# Clock.net
KiCad netlist of a schematic drawn in Altium Designer
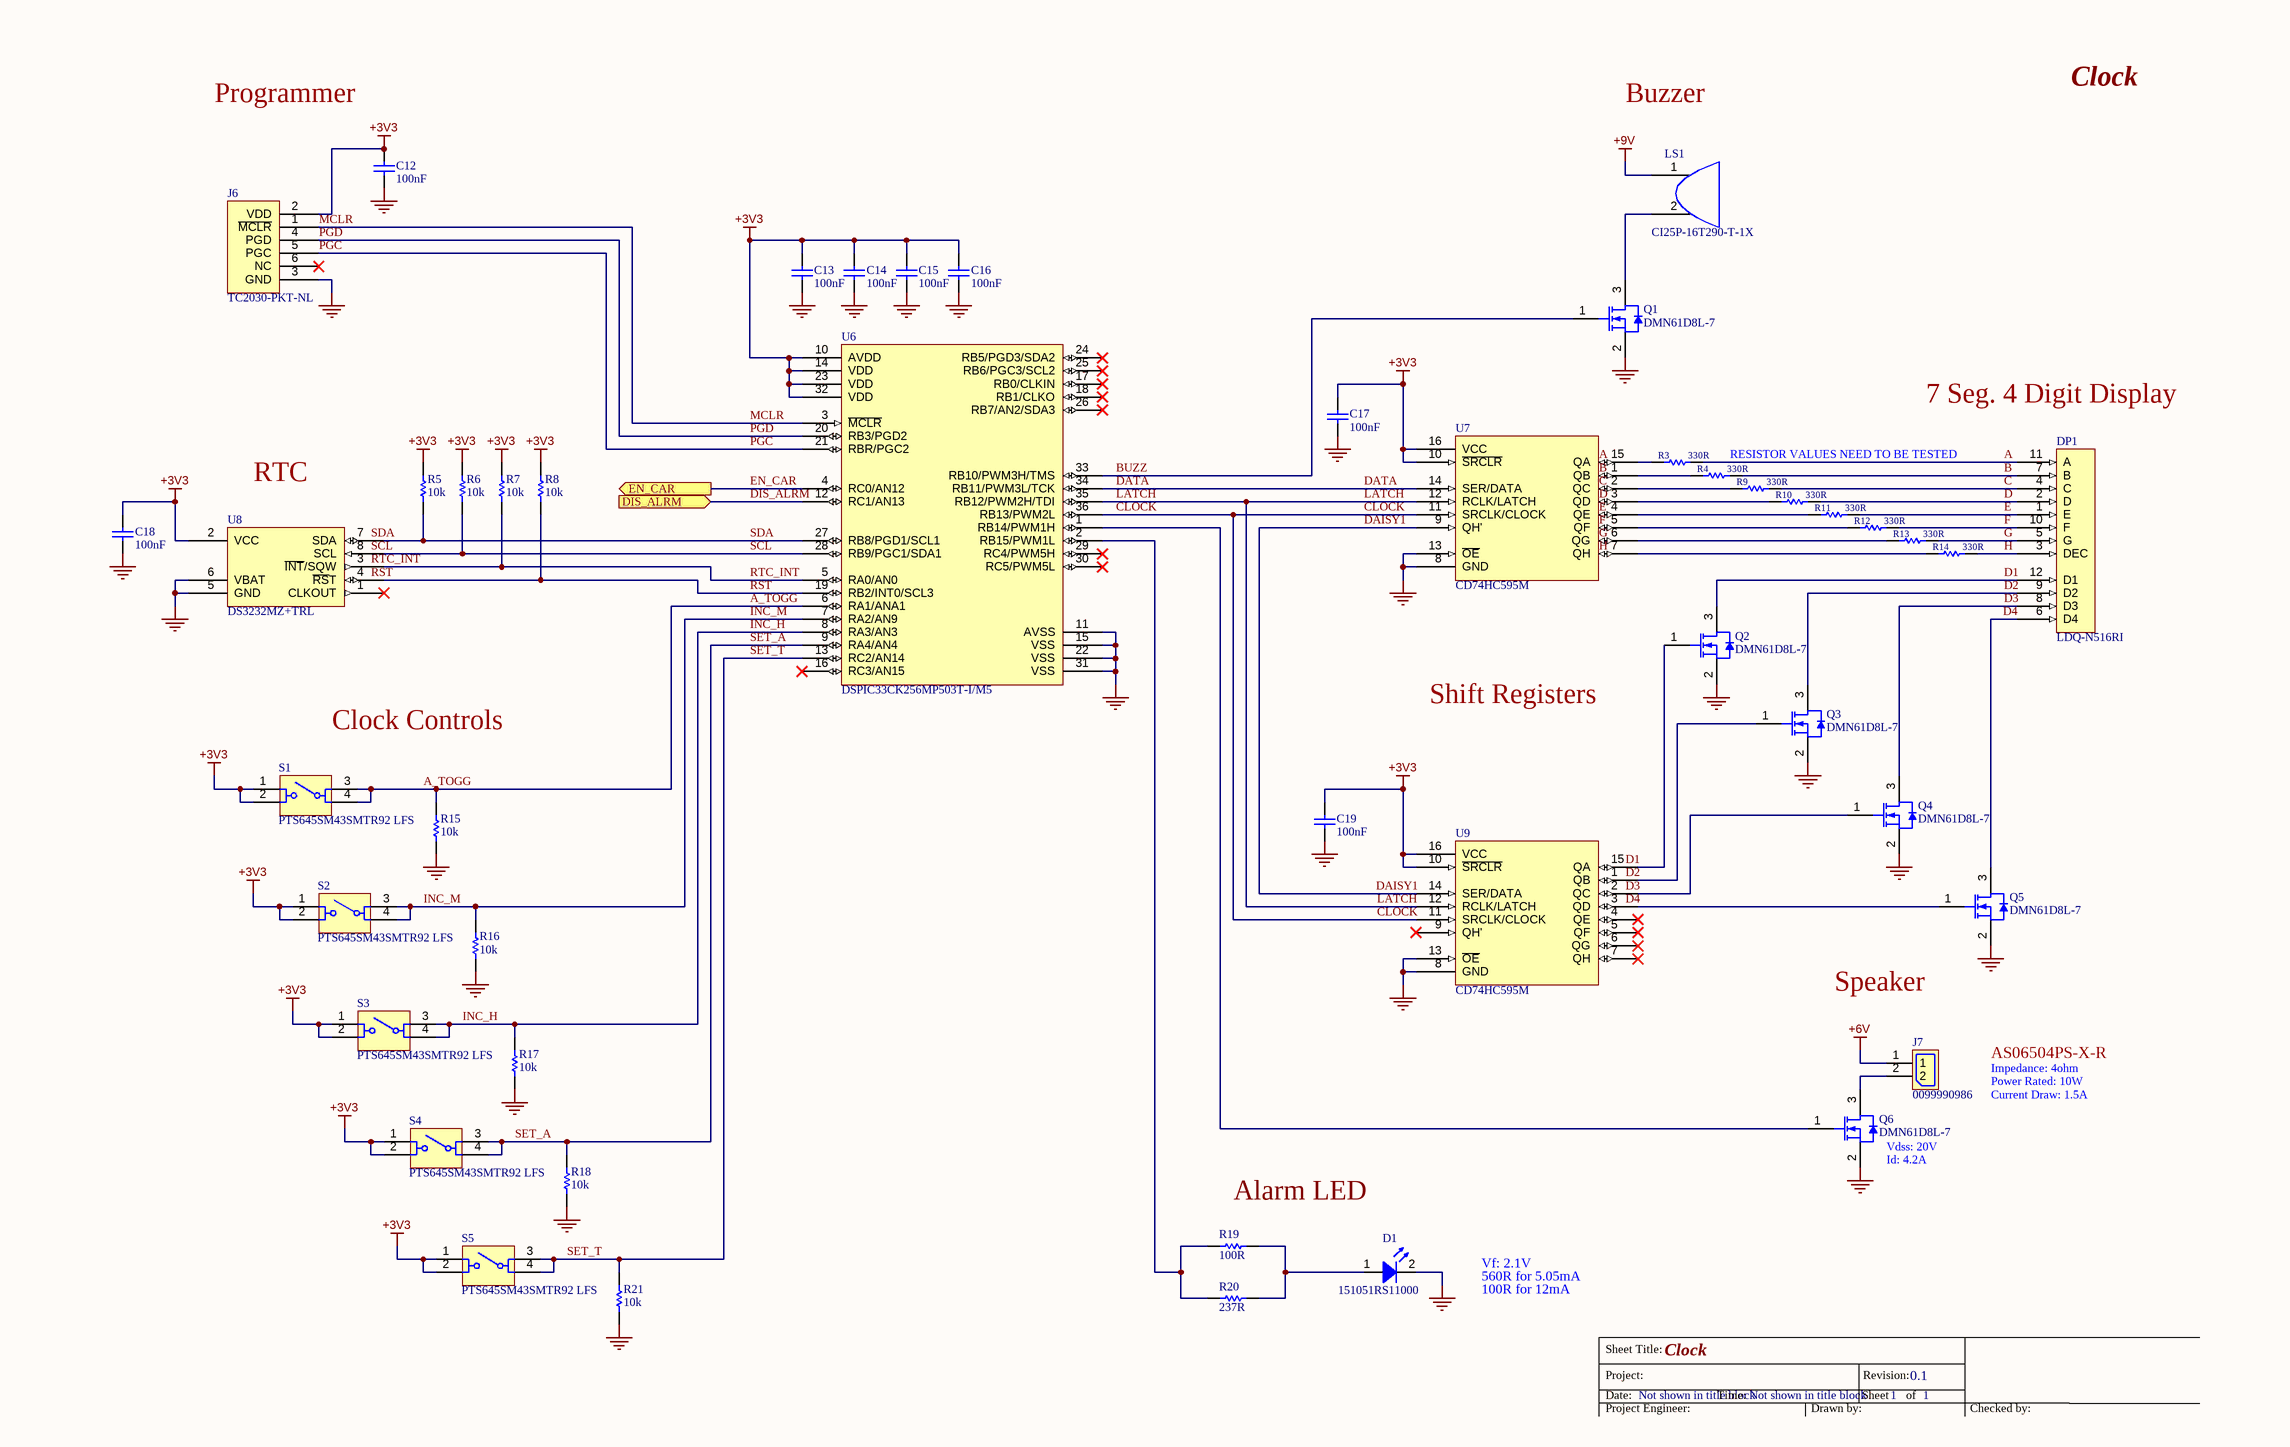
[diagram p0: Clock.SchDoc]

(export (version "E")
  (design (tool "Eeschema 10.0.6"))
  (components
    (comp (ref "C12")
      (value "100nF")
      (footprint "C0402")
      (fields (field (name "PART NUMBER") "CL05A104KA5NNNC") (field (name "MANUFACTURER") "Samsung"))
      (libsource (lib "EMRLibrary") (part "EMR_Cap"))
    )
    (comp (ref "C13")
      (value "100nF")
      (footprint "C0402")
      (fields (field (name "PART NUMBER") "CL05A104KA5NNNC") (field (name "MANUFACTURER") "Samsung"))
      (libsource (lib "EMRLibrary") (part "EMR_Cap"))
    )
    (comp (ref "C14")
      (value "100nF")
      (footprint "C0402")
      (fields (field (name "PART NUMBER") "CL05A104KA5NNNC") (field (name "MANUFACTURER") "Samsung"))
      (libsource (lib "EMRLibrary") (part "EMR_Cap"))
    )
    (comp (ref "C15")
      (value "100nF")
      (footprint "C0402")
      (fields (field (name "PART NUMBER") "CL05A104KA5NNNC") (field (name "MANUFACTURER") "Samsung"))
      (libsource (lib "EMRLibrary") (part "EMR_Cap"))
    )
    (comp (ref "C16")
      (value "100nF")
      (footprint "C0402")
      (fields (field (name "PART NUMBER") "CL05A104KA5NNNC") (field (name "MANUFACTURER") "Samsung"))
      (libsource (lib "EMRLibrary") (part "EMR_Cap"))
    )
    (comp (ref "C17")
      (value "100nF")
      (footprint "C0402")
      (fields (field (name "PART NUMBER") "CL05A104KA5NNNC") (field (name "MANUFACTURER") "Samsung"))
      (libsource (lib "EMRLibrary") (part "EMR_Cap"))
    )
    (comp (ref "C18")
      (value "100nF")
      (footprint "C0402")
      (fields (field (name "PART NUMBER") "CL05A104KA5NNNC") (field (name "MANUFACTURER") "Samsung"))
      (libsource (lib "EMRLibrary") (part "EMR_Cap"))
    )
    (comp (ref "C19")
      (value "100nF")
      (footprint "C0402")
      (fields (field (name "PART NUMBER") "CL05A104KA5NNNC") (field (name "MANUFACTURER") "Samsung"))
      (libsource (lib "EMRLibrary") (part "EMR_Cap"))
    )
    (comp (ref "D1")
      (value "151051RS11000")
      (footprint "151051RS11000")
      (fields (field (name "MANUFACTURER") "Wurth Electronics"))
      (libsource (lib "EMRLibrary") (part "EMR_LED"))
    )
    (comp (ref "DP1")
      (value "LDQ-N516RI")
      (footprint "LDQ-N516RI")
      (description "DISP 7SEG 0.56\" QUAD RED 12DIP")
      (fields (field (name "MANUFACTURER") "Lumex"))
      (libsource (lib "EMRLibrary") (part "LDQ-N516RI"))
    )
    (comp (ref "J6")
      (value "TC2030-PKT-NL")
      (footprint "TC2030-PKT-NL")
      (description "Pogo pin cable for PicKit 3")
      (libsource (lib "EMRLibrary") (part "TC2030-PKT-NL"))
    )
    (comp (ref "J7")
      (value "0099990986")
      (footprint "0099990986")
      (fields (field (name "MANUFACTURER") "Molex") (field (name "MANUFACTURER PART NUMBER") "99-99-0986"))
      (libsource (lib "EMRLibrary") (part "0099990986"))
    )
    (comp (ref "LS1")
      (value "CI25P-16T290-T-1X")
      (footprint "CI25P-16T290-T-1X")
      (description "Buzzer Piezo 12V 25.4MM Th")
      (fields (field (name "MANUFACTURER") "Challenge Electronics"))
      (libsource (lib "EMRLibrary") (part "CI25P-16T290-T-1X"))
    )
    (comp (ref "Q1")
      (value "DMN61D8L-7")
      (footprint "SOT90P240X102-3N")
      (description "MOSFET N-CH 60V 470MA SOT23")
      (fields (field (name "MANUFACTURER") "Diodes"))
      (libsource (lib "EMRLibrary") (part "BSS138L"))
    )
    (comp (ref "Q2")
      (value "DMN61D8L-7")
      (footprint "SOT90P240X102-3N")
      (description "MOSFET N-CH 60V 470MA SOT23")
      (fields (field (name "MANUFACTURER") "Diodes"))
      (libsource (lib "EMRLibrary") (part "BSS138L"))
    )
    (comp (ref "Q3")
      (value "DMN61D8L-7")
      (footprint "SOT90P240X102-3N")
      (description "MOSFET N-CH 60V 470MA SOT23")
      (fields (field (name "MANUFACTURER") "Diodes"))
      (libsource (lib "EMRLibrary") (part "BSS138L"))
    )
    (comp (ref "Q4")
      (value "DMN61D8L-7")
      (footprint "SOT90P240X102-3N")
      (description "MOSFET N-CH 60V 470MA SOT23")
      (fields (field (name "MANUFACTURER") "Diodes"))
      (libsource (lib "EMRLibrary") (part "BSS138L"))
    )
    (comp (ref "Q5")
      (value "DMN61D8L-7")
      (footprint "SOT90P240X102-3N")
      (description "MOSFET N-CH 60V 470MA SOT23")
      (fields (field (name "MANUFACTURER") "Diodes"))
      (libsource (lib "EMRLibrary") (part "BSS138L"))
    )
    (comp (ref "Q6")
      (value "DMN61D8L-7")
      (footprint "SOT90P240X102-3N")
      (description "MOSFET N-CH 60V 470MA SOT23")
      (fields (field (name "MANUFACTURER") "Diodes"))
      (libsource (lib "EMRLibrary") (part "BSS138L"))
    )
    (comp (ref "R3")
      (value "330R")
      (footprint "RESC1005X04N")
      (description "Res Thick Film 0402 330 Ohm 1% 0.063W(1/16W) ±100ppm/C Pad SMD T/R")
      (fields (field (name "PART NUMBER") "RC0402FR-07330RL") (field (name "MANUFACTURER") "Yageo"))
      (libsource (lib "EMRLibrary") (part "RC0402"))
    )
    (comp (ref "R4")
      (value "330R")
      (footprint "RESC1005X04N")
      (description "Res Thick Film 0402 330 Ohm 1% 0.063W(1/16W) ±100ppm/C Pad SMD T/R")
      (fields (field (name "PART NUMBER") "RC0402FR-07330RL") (field (name "MANUFACTURER") "Yageo"))
      (libsource (lib "EMRLibrary") (part "RC0402"))
    )
    (comp (ref "R5")
      (value "10k")
      (footprint "RESC1005X04N")
      (description "RES SMD 10K OHM 1% 1/16W 0402")
      (fields (field (name "PART NUMBER") "RC0402FR-0710KL") (field (name "MANUFACTURER") "Yageo"))
      (libsource (lib "EMRLibrary") (part "RC0402"))
    )
    (comp (ref "R6")
      (value "10k")
      (footprint "RESC1005X04N")
      (description "RES SMD 10K OHM 1% 1/16W 0402")
      (fields (field (name "PART NUMBER") "RC0402FR-0710KL") (field (name "MANUFACTURER") "Yageo"))
      (libsource (lib "EMRLibrary") (part "RC0402"))
    )
    (comp (ref "R7")
      (value "10k")
      (footprint "RESC1005X04N")
      (description "RES SMD 10K OHM 1% 1/16W 0402")
      (fields (field (name "PART NUMBER") "RC0402FR-0710KL") (field (name "MANUFACTURER") "Yageo"))
      (libsource (lib "EMRLibrary") (part "RC0402"))
    )
    (comp (ref "R8")
      (value "10k")
      (footprint "RESC1005X04N")
      (description "RES SMD 10K OHM 1% 1/16W 0402")
      (fields (field (name "PART NUMBER") "RC0402FR-0710KL") (field (name "MANUFACTURER") "Yageo"))
      (libsource (lib "EMRLibrary") (part "RC0402"))
    )
    (comp (ref "R9")
      (value "330R")
      (footprint "RESC1005X04N")
      (description "Res Thick Film 0402 330 Ohm 1% 0.063W(1/16W) ±100ppm/C Pad SMD T/R")
      (fields (field (name "PART NUMBER") "RC0402FR-07330RL") (field (name "MANUFACTURER") "Yageo"))
      (libsource (lib "EMRLibrary") (part "RC0402"))
    )
    (comp (ref "R10")
      (value "330R")
      (footprint "RESC1005X04N")
      (description "Res Thick Film 0402 330 Ohm 1% 0.063W(1/16W) ±100ppm/C Pad SMD T/R")
      (fields (field (name "PART NUMBER") "RC0402FR-07330RL") (field (name "MANUFACTURER") "Yageo"))
      (libsource (lib "EMRLibrary") (part "RC0402"))
    )
    (comp (ref "R11")
      (value "330R")
      (footprint "RESC1005X04N")
      (description "Res Thick Film 0402 330 Ohm 1% 0.063W(1/16W) ±100ppm/C Pad SMD T/R")
      (fields (field (name "PART NUMBER") "RC0402FR-07330RL") (field (name "MANUFACTURER") "Yageo"))
      (libsource (lib "EMRLibrary") (part "RC0402"))
    )
    (comp (ref "R12")
      (value "330R")
      (footprint "RESC1005X04N")
      (description "Res Thick Film 0402 330 Ohm 1% 0.063W(1/16W) ±100ppm/C Pad SMD T/R")
      (fields (field (name "PART NUMBER") "RC0402FR-07330RL") (field (name "MANUFACTURER") "Yageo"))
      (libsource (lib "EMRLibrary") (part "RC0402"))
    )
    (comp (ref "R13")
      (value "330R")
      (footprint "RESC1005X04N")
      (description "Res Thick Film 0402 330 Ohm 1% 0.063W(1/16W) ±100ppm/C Pad SMD T/R")
      (fields (field (name "PART NUMBER") "RC0402FR-07330RL") (field (name "MANUFACTURER") "Yageo"))
      (libsource (lib "EMRLibrary") (part "RC0402"))
    )
    (comp (ref "R14")
      (value "330R")
      (footprint "RESC1005X04N")
      (description "Res Thick Film 0402 330 Ohm 1% 0.063W(1/16W) ±100ppm/C Pad SMD T/R")
      (fields (field (name "PART NUMBER") "RC0402FR-07330RL") (field (name "MANUFACTURER") "Yageo"))
      (libsource (lib "EMRLibrary") (part "RC0402"))
    )
    (comp (ref "R15")
      (value "10k")
      (footprint "RESC1005X04N")
      (description "RES SMD 10K OHM 1% 1/16W 0402")
      (fields (field (name "PART NUMBER") "RC0402FR-0710KL") (field (name "MANUFACTURER") "Yageo"))
      (libsource (lib "EMRLibrary") (part "RC0402"))
    )
    (comp (ref "R16")
      (value "10k")
      (footprint "RESC1005X04N")
      (description "RES SMD 10K OHM 1% 1/16W 0402")
      (fields (field (name "PART NUMBER") "RC0402FR-0710KL") (field (name "MANUFACTURER") "Yageo"))
      (libsource (lib "EMRLibrary") (part "RC0402"))
    )
    (comp (ref "R17")
      (value "10k")
      (footprint "RESC1005X04N")
      (description "RES SMD 10K OHM 1% 1/16W 0402")
      (fields (field (name "PART NUMBER") "RC0402FR-0710KL") (field (name "MANUFACTURER") "Yageo"))
      (libsource (lib "EMRLibrary") (part "RC0402"))
    )
    (comp (ref "R18")
      (value "10k")
      (footprint "RESC1005X04N")
      (description "RES SMD 10K OHM 1% 1/16W 0402")
      (fields (field (name "PART NUMBER") "RC0402FR-0710KL") (field (name "MANUFACTURER") "Yageo"))
      (libsource (lib "EMRLibrary") (part "RC0402"))
    )
    (comp (ref "R19")
      (value "100R")
      (footprint "RESC1005X04N")
      (fields
        (field (name "PART NUMBER") "RC0402FR-07100RL")
        (field (name "MANUFACTURER") "Yageo")
        (field (name "TOLERANCE") "1%")
      )
      (libsource (lib "EMRLibrary") (part "RC0402"))
    )
    (comp (ref "R20")
      (value "237R")
      (footprint "RESC1005X04N")
      (description "Thick Film Resistors - SMD 237 OHM 1%")
      (fields (field (name "PART NUMBER") "RC0402FR-07237RL") (field (name "MANUFACTURER") "Yageo"))
      (libsource (lib "EMRLibrary") (part "RC0402"))
    )
    (comp (ref "R21")
      (value "10k")
      (footprint "RESC1005X04N")
      (description "RES SMD 10K OHM 1% 1/16W 0402")
      (fields (field (name "PART NUMBER") "RC0402FR-0710KL") (field (name "MANUFACTURER") "Yageo"))
      (libsource (lib "EMRLibrary") (part "RC0402"))
    )
    (comp (ref "S1")
      (value "PTS645SM43SMTR92 LFS")
      (footprint "PTS645SM43SMTR92 LFS")
      (description "RED TACTILE SWTICH - SMD")
      (fields (field (name "PART NUMBER") "PTS645SK50SMTR92LFS") (field (name "MANUFACTURER") "ITT C&K"))
      (libsource (lib "EMRLibrary") (part "PTS645SM43SMTR92 LFS"))
    )
    (comp (ref "S2")
      (value "PTS645SM43SMTR92 LFS")
      (footprint "PTS645SM43SMTR92 LFS")
      (description "BLACK TACTILE SWTICH - SMD")
      (fields (field (name "PART NUMBER") "PTS645SL50SMTR92LFS") (field (name "MANUFACTURER") "ITT C&K"))
      (libsource (lib "EMRLibrary") (part "PTS645SM43SMTR92 LFS"))
    )
    (comp (ref "S3")
      (value "PTS645SM43SMTR92 LFS")
      (footprint "PTS645SM43SMTR92 LFS")
      (description "BLACK TACTILE SWTICH - SMD")
      (fields (field (name "PART NUMBER") "PTS645SL50SMTR92LFS") (field (name "MANUFACTURER") "ITT C&K"))
      (libsource (lib "EMRLibrary") (part "PTS645SM43SMTR92 LFS"))
    )
    (comp (ref "S4")
      (value "PTS645SM43SMTR92 LFS")
      (footprint "PTS645SM43SMTR92 LFS")
      (description "BLACK TACTILE SWTICH - SMD")
      (fields (field (name "PART NUMBER") "PTS645SL50SMTR92LFS") (field (name "MANUFACTURER") "ITT C&K"))
      (libsource (lib "EMRLibrary") (part "PTS645SM43SMTR92 LFS"))
    )
    (comp (ref "S5")
      (value "PTS645SM43SMTR92 LFS")
      (footprint "PTS645SM43SMTR92 LFS")
      (description "BLACK TACTILE SWTICH - SMD")
      (fields (field (name "PART NUMBER") "PTS645SL50SMTR92LFS") (field (name "MANUFACTURER") "ITT C&K"))
      (libsource (lib "EMRLibrary") (part "PTS645SM43SMTR92 LFS"))
    )
    (comp (ref "U6")
      (value "DSPIC33CK256MP503T-I/M5")
      (footprint "QFN40P500X500X60_HS-37N")
      (description "MCU 16-Bit dsPIC DSC Modified Harvard Architecture 256KB Flash 3V to 3.6V 36-Pin UQFN T/R")
      (fields (field (name "MANUFACTURER") "Microchip"))
      (libsource (lib "EMRLibrary") (part "DSPIC33CK256MP503T-I/M5"))
    )
    (comp (ref "U7")
      (value "CD74HC595M")
      (description "Shift Shift Register 1 Element 8 Bit 16-SOIC")
      (libsource (lib "EMR") (part "CD74HC595M"))
    )
    (comp (ref "U8")
      (value "DS3232MZ+TRL")
      (description "IC RTC CLK/CALENDAR I2C 8-SOIC")
      (libsource (lib "EMR") (part "DS3232MZ+TRL"))
    )
    (comp (ref "U9")
      (value "CD74HC595M")
      (description "Shift Shift Register 1 Element 8 Bit 16-SOIC")
      (libsource (lib "EMR") (part "CD74HC595M"))
    )
  )
  (nets
    (net (code "1") (name "+3V3") (class "Default")
      (node (ref "C12") (pin "2") (pinfunction "2_2") (pintype "passive"))
      (node (ref "C13") (pin "2") (pinfunction "2_2") (pintype "passive"))
      (node (ref "C14") (pin "2") (pinfunction "2_2") (pintype "passive"))
      (node (ref "C15") (pin "2") (pinfunction "2_2") (pintype "passive"))
      (node (ref "C16") (pin "2") (pinfunction "2_2") (pintype "passive"))
      (node (ref "C17") (pin "2") (pinfunction "2_2") (pintype "passive"))
      (node (ref "C18") (pin "2") (pinfunction "2_2") (pintype "passive"))
      (node (ref "C19") (pin "2") (pinfunction "2_2") (pintype "passive"))
      (node (ref "J6") (pin "2") (pinfunction "VDD_2") (pintype "passive"))
      (node (ref "R5") (pin "2") (pinfunction "2_2") (pintype "passive"))
      (node (ref "R6") (pin "2") (pinfunction "2_2") (pintype "passive"))
      (node (ref "R7") (pin "2") (pinfunction "2_2") (pintype "passive"))
      (node (ref "R8") (pin "2") (pinfunction "2_2") (pintype "passive"))
      (node (ref "S1") (pin "1") (pinfunction "1_1") (pintype "passive"))
      (node (ref "S1") (pin "2") (pinfunction "2_2") (pintype "passive"))
      (node (ref "S2") (pin "1") (pinfunction "1_1") (pintype "passive"))
      (node (ref "S2") (pin "2") (pinfunction "2_2") (pintype "passive"))
      (node (ref "S3") (pin "1") (pinfunction "1_1") (pintype "passive"))
      (node (ref "S3") (pin "2") (pinfunction "2_2") (pintype "passive"))
      (node (ref "S4") (pin "1") (pinfunction "1_1") (pintype "passive"))
      (node (ref "S4") (pin "2") (pinfunction "2_2") (pintype "passive"))
      (node (ref "S5") (pin "1") (pinfunction "1_1") (pintype "passive"))
      (node (ref "S5") (pin "2") (pinfunction "2_2") (pintype "passive"))
      (node (ref "U6") (pin "10") (pinfunction "AVDD_10") (pintype "power_in"))
      (node (ref "U6") (pin "14") (pinfunction "VDD_14") (pintype "power_in"))
      (node (ref "U6") (pin "23") (pinfunction "VDD_23") (pintype "power_in"))
      (node (ref "U6") (pin "32") (pinfunction "VDD_32") (pintype "power_in"))
      (node (ref "U7") (pin "10") (pinfunction "~{SRCLR}_10") (pintype "input"))
      (node (ref "U7") (pin "16") (pinfunction "VCC_16") (pintype "power_in"))
      (node (ref "U8") (pin "2") (pinfunction "VCC_2") (pintype "power_in"))
      (node (ref "U9") (pin "10") (pinfunction "~{SRCLR}_10") (pintype "input"))
      (node (ref "U9") (pin "16") (pinfunction "VCC_16") (pintype "power_in"))
    )
    (net (code "2") (name "+6V") (class "Default")
      (node (ref "J7") (pin "1") (pinfunction "1_1") (pintype "passive"))
    )
    (net (code "3") (name "+9V") (class "Default")
      (node (ref "LS1") (pin "1") (pinfunction "VCC_1") (pintype "power_in"))
    )
    (net (code "4") (name "/A") (class "Default")
      (node (ref "DP1") (pin "11") (pinfunction "A_11") (pintype "input"))
      (node (ref "R3") (pin "2") (pinfunction "2_2") (pintype "passive"))
    )
    (net (code "5") (name "/A_TOGG") (class "Default")
      (node (ref "R15") (pin "2") (pinfunction "2_2") (pintype "passive"))
      (node (ref "S1") (pin "3") (pinfunction "3_3") (pintype "passive"))
      (node (ref "S1") (pin "4") (pinfunction "4_4") (pintype "passive"))
      (node (ref "U6") (pin "6") (pinfunction "RA1/ANA1_6") (pintype "bidirectional"))
    )
    (net (code "7") (name "/B") (class "Default")
      (node (ref "DP1") (pin "7") (pinfunction "B_7") (pintype "input"))
      (node (ref "R4") (pin "2") (pinfunction "2_2") (pintype "passive"))
    )
    (net (code "8") (name "/BUZZ") (class "Default")
      (node (ref "Q1") (pin "1") (pinfunction "G_1") (pintype "passive"))
      (node (ref "U6") (pin "33") (pinfunction "RB10/PWM3H/TMS_33") (pintype "bidirectional"))
    )
    (net (code "9") (name "/C") (class "Default")
      (node (ref "DP1") (pin "4") (pinfunction "C_4") (pintype "input"))
      (node (ref "R9") (pin "2") (pinfunction "2_2") (pintype "passive"))
    )
    (net (code "10") (name "/CLOCK") (class "Default")
      (node (ref "U6") (pin "36") (pinfunction "RB13/PWM2L_36") (pintype "bidirectional"))
      (node (ref "U7") (pin "11") (pinfunction "SRCLK/CLOCK_11") (pintype "input"))
      (node (ref "U9") (pin "11") (pinfunction "SRCLK/CLOCK_11") (pintype "input"))
    )
    (net (code "11") (name "/D") (class "Default")
      (node (ref "DP1") (pin "2") (pinfunction "D_2") (pintype "input"))
      (node (ref "R10") (pin "2") (pinfunction "2_2") (pintype "passive"))
    )
    (net (code "12") (name "/D1") (class "Default")
      (node (ref "DP1") (pin "12") (pinfunction "D1_12") (pintype "input"))
      (node (ref "Q2") (pin "3") (pinfunction "D_3") (pintype "passive"))
    )
    (net (code "13") (name "/D2") (class "Default")
      (node (ref "DP1") (pin "9") (pinfunction "D2_9") (pintype "input"))
      (node (ref "Q3") (pin "3") (pinfunction "D_3") (pintype "passive"))
    )
    (net (code "14") (name "/D3") (class "Default")
      (node (ref "DP1") (pin "8") (pinfunction "D3_8") (pintype "input"))
      (node (ref "Q4") (pin "3") (pinfunction "D_3") (pintype "passive"))
    )
    (net (code "15") (name "/D4") (class "Default")
      (node (ref "DP1") (pin "6") (pinfunction "D4_6") (pintype "input"))
      (node (ref "Q5") (pin "3") (pinfunction "D_3") (pintype "passive"))
    )
    (net (code "16") (name "/DAISY1") (class "Default")
      (node (ref "U7") (pin "9") (pinfunction "QH'_9") (pintype "input"))
      (node (ref "U9") (pin "14") (pinfunction "SER/DATA_14") (pintype "input"))
    )
    (net (code "17") (name "/DATA") (class "Default")
      (node (ref "U6") (pin "34") (pinfunction "RB11/PWM3L/TCK_34") (pintype "bidirectional"))
      (node (ref "U7") (pin "14") (pinfunction "SER/DATA_14") (pintype "input"))
    )
    (net (code "18") (name "/DIS_ALRM") (class "Default")
      (node (ref "U6") (pin "12") (pinfunction "RC1/AN13_12") (pintype "bidirectional"))
    )
    (net (code "19") (name "/E") (class "Default")
      (node (ref "DP1") (pin "1") (pinfunction "E_1") (pintype "input"))
      (node (ref "R11") (pin "2") (pinfunction "2_2") (pintype "passive"))
    )
    (net (code "20") (name "/EN_CAR") (class "Default")
      (node (ref "U6") (pin "4") (pinfunction "RC0/AN12_4") (pintype "bidirectional"))
    )
    (net (code "21") (name "/F") (class "Default")
      (node (ref "DP1") (pin "10") (pinfunction "F_10") (pintype "input"))
      (node (ref "R12") (pin "2") (pinfunction "2_2") (pintype "passive"))
    )
    (net (code "22") (name "/G") (class "Default")
      (node (ref "DP1") (pin "5") (pinfunction "G_5") (pintype "input"))
      (node (ref "R13") (pin "2") (pinfunction "2_2") (pintype "passive"))
    )
    (net (code "23") (name "/H") (class "Default")
      (node (ref "DP1") (pin "3") (pinfunction "DEC_3") (pintype "input"))
      (node (ref "R14") (pin "2") (pinfunction "2_2") (pintype "passive"))
    )
    (net (code "24") (name "/INC_H") (class "Default")
      (node (ref "R17") (pin "2") (pinfunction "2_2") (pintype "passive"))
      (node (ref "S3") (pin "3") (pinfunction "3_3") (pintype "passive"))
      (node (ref "S3") (pin "4") (pinfunction "4_4") (pintype "passive"))
      (node (ref "U6") (pin "8") (pinfunction "RA3/AN3_8") (pintype "bidirectional"))
    )
    (net (code "25") (name "/INC_M") (class "Default")
      (node (ref "R16") (pin "2") (pinfunction "2_2") (pintype "passive"))
      (node (ref "S2") (pin "3") (pinfunction "3_3") (pintype "passive"))
      (node (ref "S2") (pin "4") (pinfunction "4_4") (pintype "passive"))
      (node (ref "U6") (pin "7") (pinfunction "RA2/AN9_7") (pintype "bidirectional"))
    )
    (net (code "26") (name "/LATCH") (class "Default")
      (node (ref "U6") (pin "35") (pinfunction "RB12/PWM2H/TDI_35") (pintype "bidirectional"))
      (node (ref "U7") (pin "12") (pinfunction "RCLK/LATCH_12") (pintype "input"))
      (node (ref "U9") (pin "12") (pinfunction "RCLK/LATCH_12") (pintype "input"))
    )
    (net (code "27") (name "/MCLR") (class "Default")
      (node (ref "J6") (pin "1") (pinfunction "~{MCLR}_1") (pintype "passive"))
      (node (ref "U6") (pin "3") (pinfunction "~{MCLR}_3") (pintype "input"))
    )
    (net (code "28") (name "/PGC") (class "Default")
      (node (ref "J6") (pin "5") (pinfunction "PGC_5") (pintype "passive"))
      (node (ref "U6") (pin "21") (pinfunction "RBR/PGC2_21") (pintype "bidirectional"))
    )
    (net (code "29") (name "/PGD") (class "Default")
      (node (ref "J6") (pin "4") (pinfunction "PGD_4") (pintype "passive"))
      (node (ref "U6") (pin "20") (pinfunction "RB3/PGD2_20") (pintype "bidirectional"))
    )
    (net (code "30") (name "/RST") (class "Default")
      (node (ref "R8") (pin "1") (pinfunction "1_1") (pintype "passive"))
      (node (ref "U6") (pin "19") (pinfunction "RB2/INT0/SCL3_19") (pintype "bidirectional"))
      (node (ref "U8") (pin "4") (pinfunction "~{RS}T_4") (pintype "bidirectional"))
    )
    (net (code "31") (name "/RTC_INT") (class "Default")
      (node (ref "R7") (pin "1") (pinfunction "1_1") (pintype "passive"))
      (node (ref "U6") (pin "5") (pinfunction "RA0/AN0_5") (pintype "bidirectional"))
      (node (ref "U8") (pin "3") (pinfunction "~{INT}/SQW_3") (pintype "output"))
    )
    (net (code "32") (name "/SCL") (class "Default")
      (node (ref "R6") (pin "1") (pinfunction "1_1") (pintype "passive"))
      (node (ref "U6") (pin "28") (pinfunction "RB9/PGC1/SDA1_28") (pintype "bidirectional"))
      (node (ref "U8") (pin "8") (pinfunction "SCL_8") (pintype "input"))
    )
    (net (code "33") (name "/SDA") (class "Default")
      (node (ref "R5") (pin "1") (pinfunction "1_1") (pintype "passive"))
      (node (ref "U6") (pin "27") (pinfunction "RB8/PGD1/SCL1_27") (pintype "bidirectional"))
      (node (ref "U8") (pin "7") (pinfunction "SDA_7") (pintype "bidirectional"))
    )
    (net (code "34") (name "/SET_A") (class "Default")
      (node (ref "R18") (pin "2") (pinfunction "2_2") (pintype "passive"))
      (node (ref "S4") (pin "3") (pinfunction "3_3") (pintype "passive"))
      (node (ref "S4") (pin "4") (pinfunction "4_4") (pintype "passive"))
      (node (ref "U6") (pin "9") (pinfunction "RA4/AN4_9") (pintype "bidirectional"))
    )
    (net (code "35") (name "/SET_T") (class "Default")
      (node (ref "R21") (pin "2") (pinfunction "2_2") (pintype "passive"))
      (node (ref "S5") (pin "3") (pinfunction "3_3") (pintype "passive"))
      (node (ref "S5") (pin "4") (pinfunction "4_4") (pintype "passive"))
      (node (ref "U6") (pin "13") (pinfunction "RC2/AN14_13") (pintype "bidirectional"))
    )
    (net (code "36") (name "GND") (class "Default")
      (node (ref "C12") (pin "1") (pinfunction "1_1") (pintype "passive"))
      (node (ref "C13") (pin "1") (pinfunction "1_1") (pintype "passive"))
      (node (ref "C14") (pin "1") (pinfunction "1_1") (pintype "passive"))
      (node (ref "C15") (pin "1") (pinfunction "1_1") (pintype "passive"))
      (node (ref "C16") (pin "1") (pinfunction "1_1") (pintype "passive"))
      (node (ref "C17") (pin "1") (pinfunction "1_1") (pintype "passive"))
      (node (ref "C18") (pin "1") (pinfunction "1_1") (pintype "passive"))
      (node (ref "C19") (pin "1") (pinfunction "1_1") (pintype "passive"))
      (node (ref "D1") (pin "2") (pinfunction "K_2") (pintype "passive"))
      (node (ref "J6") (pin "3") (pinfunction "GND_3") (pintype "passive"))
      (node (ref "Q1") (pin "2") (pinfunction "S_2") (pintype "passive"))
      (node (ref "Q2") (pin "2") (pinfunction "S_2") (pintype "passive"))
      (node (ref "Q3") (pin "2") (pinfunction "S_2") (pintype "passive"))
      (node (ref "Q4") (pin "2") (pinfunction "S_2") (pintype "passive"))
      (node (ref "Q5") (pin "2") (pinfunction "S_2") (pintype "passive"))
      (node (ref "Q6") (pin "2") (pinfunction "S_2") (pintype "passive"))
      (node (ref "R15") (pin "1") (pinfunction "1_1") (pintype "passive"))
      (node (ref "R16") (pin "1") (pinfunction "1_1") (pintype "passive"))
      (node (ref "R17") (pin "1") (pinfunction "1_1") (pintype "passive"))
      (node (ref "R18") (pin "1") (pinfunction "1_1") (pintype "passive"))
      (node (ref "R21") (pin "1") (pinfunction "1_1") (pintype "passive"))
      (node (ref "U6") (pin "11") (pinfunction "AVSS_11") (pintype "power_in"))
      (node (ref "U6") (pin "15") (pinfunction "VSS_15") (pintype "power_in"))
      (node (ref "U6") (pin "22") (pinfunction "VSS_22") (pintype "power_in"))
      (node (ref "U6") (pin "31") (pinfunction "VSS_31") (pintype "power_in"))
      (node (ref "U7") (pin "13") (pinfunction "~{OE}_13") (pintype "input"))
      (node (ref "U7") (pin "8") (pinfunction "GND_8") (pintype "power_in"))
      (node (ref "U8") (pin "5") (pinfunction "GND_5") (pintype "power_in"))
      (node (ref "U8") (pin "6") (pinfunction "VBAT_6") (pintype "power_in"))
      (node (ref "U9") (pin "13") (pinfunction "~{OE}_13") (pintype "input"))
      (node (ref "U9") (pin "8") (pinfunction "GND_8") (pintype "power_in"))
    )
    (net (code "37") (name "Net-(D1-A)") (class "Default")
      (node (ref "D1") (pin "1") (pinfunction "A_1") (pintype "passive"))
      (node (ref "R19") (pin "2") (pinfunction "2_2") (pintype "passive"))
      (node (ref "R20") (pin "2") (pinfunction "2_2") (pintype "passive"))
    )
    (net (code "38") (name "Net-(LS1-GND)") (class "Default")
      (node (ref "LS1") (pin "2") (pinfunction "GND_2") (pintype "power_in"))
      (node (ref "Q1") (pin "3") (pinfunction "D_3") (pintype "passive"))
    )
    (net (code "39") (name "Net-(Q2-G)") (class "Default")
      (node (ref "Q2") (pin "1") (pinfunction "G_1") (pintype "passive"))
      (node (ref "U9") (pin "15") (pinfunction "QA_15") (pintype "bidirectional"))
    )
    (net (code "40") (name "Net-(Q3-G)") (class "Default")
      (node (ref "Q3") (pin "1") (pinfunction "G_1") (pintype "passive"))
      (node (ref "U9") (pin "1") (pinfunction "QB_1") (pintype "bidirectional"))
    )
    (net (code "41") (name "Net-(Q4-G)") (class "Default")
      (node (ref "Q4") (pin "1") (pinfunction "G_1") (pintype "passive"))
      (node (ref "U9") (pin "2") (pinfunction "QC_2") (pintype "bidirectional"))
    )
    (net (code "42") (name "Net-(Q5-G)") (class "Default")
      (node (ref "Q5") (pin "1") (pinfunction "G_1") (pintype "passive"))
      (node (ref "U9") (pin "3") (pinfunction "QD_3") (pintype "bidirectional"))
    )
    (net (code "43") (name "Net-(Q6-D)") (class "Default")
      (node (ref "J7") (pin "2") (pinfunction "2_2") (pintype "passive"))
      (node (ref "Q6") (pin "3") (pinfunction "D_3") (pintype "passive"))
    )
    (net (code "44") (name "Net-(Q6-G)") (class "Default")
      (node (ref "Q6") (pin "1") (pinfunction "G_1") (pintype "passive"))
      (node (ref "U6") (pin "1") (pinfunction "RB14/PWM1H_1") (pintype "bidirectional"))
    )
    (net (code "45") (name "Net-(U6-RB15{slash}PWM1L)") (class "Default")
      (node (ref "R19") (pin "1") (pinfunction "1_1") (pintype "passive"))
      (node (ref "R20") (pin "1") (pinfunction "1_1") (pintype "passive"))
      (node (ref "U6") (pin "2") (pinfunction "RB15/PWM1L_2") (pintype "bidirectional"))
    )
    (net (code "46") (name "Net-(U7-QA)") (class "Default")
      (node (ref "R3") (pin "1") (pinfunction "1_1") (pintype "passive"))
      (node (ref "U7") (pin "15") (pinfunction "QA_15") (pintype "bidirectional"))
    )
    (net (code "47") (name "Net-(U7-QB)") (class "Default")
      (node (ref "R4") (pin "1") (pinfunction "1_1") (pintype "passive"))
      (node (ref "U7") (pin "1") (pinfunction "QB_1") (pintype "bidirectional"))
    )
    (net (code "48") (name "Net-(U7-QC)") (class "Default")
      (node (ref "R9") (pin "1") (pinfunction "1_1") (pintype "passive"))
      (node (ref "U7") (pin "2") (pinfunction "QC_2") (pintype "bidirectional"))
    )
    (net (code "49") (name "Net-(U7-QD)") (class "Default")
      (node (ref "R10") (pin "1") (pinfunction "1_1") (pintype "passive"))
      (node (ref "U7") (pin "3") (pinfunction "QD_3") (pintype "bidirectional"))
    )
    (net (code "50") (name "Net-(U7-QE)") (class "Default")
      (node (ref "R11") (pin "1") (pinfunction "1_1") (pintype "passive"))
      (node (ref "U7") (pin "4") (pinfunction "QE_4") (pintype "bidirectional"))
    )
    (net (code "51") (name "Net-(U7-QF)") (class "Default")
      (node (ref "R12") (pin "1") (pinfunction "1_1") (pintype "passive"))
      (node (ref "U7") (pin "5") (pinfunction "QF_5") (pintype "bidirectional"))
    )
    (net (code "52") (name "Net-(U7-QG)") (class "Default")
      (node (ref "R13") (pin "1") (pinfunction "1_1") (pintype "passive"))
      (node (ref "U7") (pin "6") (pinfunction "QG_6") (pintype "bidirectional"))
    )
    (net (code "53") (name "Net-(U7-QH)") (class "Default")
      (node (ref "R14") (pin "1") (pinfunction "1_1") (pintype "passive"))
      (node (ref "U7") (pin "7") (pinfunction "QH_7") (pintype "bidirectional"))
    )
    (net (code "54") (name "unconnected-(J6-NC-Pad6)") (class "Default")
      (node (ref "J6") (pin "6") (pinfunction "NC_6") (pintype "passive+no_connect"))
    )
    (net (code "55") (name "unconnected-(U6-RB0{slash}CLKIN-Pad17)") (class "Default")
      (node (ref "U6") (pin "17") (pinfunction "RB0/CLKIN_17") (pintype "bidirectional+no_connect"))
    )
    (net (code "56") (name "unconnected-(U6-RB1{slash}CLKO-Pad18)") (class "Default")
      (node (ref "U6") (pin "18") (pinfunction "RB1/CLKO_18") (pintype "bidirectional+no_connect"))
    )
    (net (code "57") (name "unconnected-(U6-RB5{slash}PGD3{slash}SDA2-Pad24)") (class "Default")
      (node (ref "U6") (pin "24") (pinfunction "RB5/PGD3/SDA2_24") (pintype "bidirectional+no_connect"))
    )
    (net (code "58") (name "unconnected-(U6-RB6{slash}PGC3{slash}SCL2-Pad25)") (class "Default")
      (node (ref "U6") (pin "25") (pinfunction "RB6/PGC3/SCL2_25") (pintype "bidirectional+no_connect"))
    )
    (net (code "59") (name "unconnected-(U6-RB7{slash}AN2{slash}SDA3-Pad26)") (class "Default")
      (node (ref "U6") (pin "26") (pinfunction "RB7/AN2/SDA3_26") (pintype "bidirectional+no_connect"))
    )
    (net (code "60") (name "unconnected-(U6-RC3{slash}AN15-Pad16)") (class "Default")
      (node (ref "U6") (pin "16") (pinfunction "RC3/AN15_16") (pintype "bidirectional+no_connect"))
    )
    (net (code "61") (name "unconnected-(U6-RC4{slash}PWM5H-Pad29)") (class "Default")
      (node (ref "U6") (pin "29") (pinfunction "RC4/PWM5H_29") (pintype "bidirectional+no_connect"))
    )
    (net (code "62") (name "unconnected-(U6-RC5{slash}PWM5L-Pad30)") (class "Default")
      (node (ref "U6") (pin "30") (pinfunction "RC5/PWM5L_30") (pintype "bidirectional+no_connect"))
    )
    (net (code "63") (name "unconnected-(U8-CLKOUT-Pad1)") (class "Default")
      (node (ref "U8") (pin "1") (pinfunction "CLKOUT_1") (pintype "output+no_connect"))
    )
    (net (code "64") (name "unconnected-(U9-QE-Pad4)") (class "Default")
      (node (ref "U9") (pin "4") (pinfunction "QE_4") (pintype "bidirectional+no_connect"))
    )
    (net (code "65") (name "unconnected-(U9-QF-Pad5)") (class "Default")
      (node (ref "U9") (pin "5") (pinfunction "QF_5") (pintype "bidirectional+no_connect"))
    )
    (net (code "66") (name "unconnected-(U9-QG-Pad6)") (class "Default")
      (node (ref "U9") (pin "6") (pinfunction "QG_6") (pintype "bidirectional+no_connect"))
    )
    (net (code "67") (name "unconnected-(U9-QH'-Pad9)") (class "Default")
      (node (ref "U9") (pin "9") (pinfunction "QH'_9") (pintype "input+no_connect"))
    )
    (net (code "68") (name "unconnected-(U9-QH-Pad7)") (class "Default")
      (node (ref "U9") (pin "7") (pinfunction "QH_7") (pintype "bidirectional+no_connect"))
    )
  )
)
